# ZVS_Flyback_Driver_Circuit.net
KiCad netlist of a schematic drawn in EAGLE
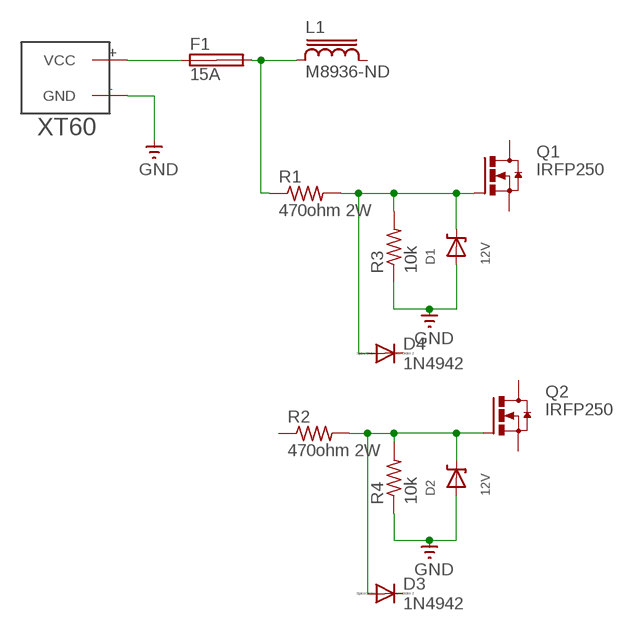
[diagram p0: schematic, sheet 1]

(export (version "E")
  (design (tool "Eeschema 10.0.6"))
  (components
    (comp (ref "D1")
      (value "12V")
      (footprint "eagle-import:SMADIODE")
      (libsource (lib "eagle-import") (part "DIODE-ZENER"))
    )
    (comp (ref "D2")
      (value "12V")
      (footprint "eagle-import:SMADIODE")
      (libsource (lib "eagle-import") (part "DIODE-ZENER"))
    )
    (comp (ref "D3")
      (value "1N4942")
      (footprint "eagle-import:DO41-10")
      (libsource (lib "eagle-import") (part "1N4942"))
    )
    (comp (ref "D4")
      (value "1N4942")
      (footprint "eagle-import:DO41-10")
      (libsource (lib "eagle-import") (part "1N4942"))
    )
    (comp (ref "F1")
      (value "15A")
      (footprint "eagle-import:SHK20L")
      (libsource (lib "eagle-import") (part "SHK20L"))
    )
    (comp (ref "L1")
      (value "M8936-ND")
      (footprint "eagle-import:2320-V-RC")
      (libsource (lib "eagle-import") (part "2300-V"))
    )
    (comp (ref "Q1")
      (value "IRFP250")
      (footprint "eagle-import:TO-247AD-V")
      (libsource (lib "eagle-import") (part "IRFP250"))
    )
    (comp (ref "Q2")
      (value "IRFP250")
      (footprint "eagle-import:TO-247AD-V")
      (libsource (lib "eagle-import") (part "IRFP250"))
    )
    (comp (ref "R1")
      (value "470ohm 2W")
      (footprint "eagle-import:0617_22")
      (libsource (lib "eagle-import") (part "R-US_0617/22"))
    )
    (comp (ref "R2")
      (value "470ohm 2W")
      (footprint "eagle-import:0617_22")
      (libsource (lib "eagle-import") (part "R-US_0617/22"))
    )
    (comp (ref "R3")
      (value "10k")
      (footprint "eagle-import:M0805")
      (libsource (lib "eagle-import") (part "R-US_M0805"))
    )
    (comp (ref "R4")
      (value "10k")
      (footprint "eagle-import:M0805")
      (libsource (lib "eagle-import") (part "R-US_M0805"))
    )
    (comp (ref "U$1")
      (value "XT60")
      (footprint "eagle-import:XT60")
      (libsource (lib "eagle-import") (part "XT60"))
    )
  )
  (nets
    (net (code "1") (name "GND") (class "Default")
      (node (ref "D1") (pin "A") (pinfunction "A_A") (pintype "passive"))
      (node (ref "D2") (pin "A") (pinfunction "A_A") (pintype "passive"))
      (node (ref "R3") (pin "1") (pinfunction "1_1") (pintype "passive"))
      (node (ref "R4") (pin "1") (pinfunction "1_1") (pintype "passive"))
      (node (ref "U$1") (pin "-") (pinfunction "GND_-") (pintype "bidirectional"))
    )
    (net (code "2") (name "Net-(D1-PadC)") (class "Default")
      (node (ref "D1") (pin "C") (pinfunction "C_C") (pintype "passive"))
      (node (ref "D4") (pin "A") (pinfunction "A_A") (pintype "passive"))
      (node (ref "Q1") (pin "G") (pinfunction "G_G") (pintype "passive"))
      (node (ref "R1") (pin "2") (pinfunction "2_2") (pintype "passive"))
      (node (ref "R3") (pin "2") (pinfunction "2_2") (pintype "passive"))
    )
    (net (code "3") (name "Net-(D2-PadC)") (class "Default")
      (node (ref "D2") (pin "C") (pinfunction "C_C") (pintype "passive"))
      (node (ref "D3") (pin "A") (pinfunction "A_A") (pintype "passive"))
      (node (ref "Q2") (pin "G") (pinfunction "G_G") (pintype "passive"))
      (node (ref "R2") (pin "2") (pinfunction "2_2") (pintype "passive"))
      (node (ref "R4") (pin "2") (pinfunction "2_2") (pintype "passive"))
    )
    (net (code "4") (name "Net-(F1-Pad2A)") (class "Default")
      (node (ref "F1") (pin "2A") (pinfunction "2A_2A") (pintype "passive"))
      (node (ref "L1") (pin "1") (pinfunction "1_1") (pintype "passive"))
      (node (ref "R1") (pin "1") (pinfunction "1_1") (pintype "passive"))
    )
    (net (code "5") (name "Net-(U$1-VCC)") (class "Default")
      (node (ref "F1") (pin "1A") (pinfunction "1A_1A") (pintype "passive"))
      (node (ref "U$1") (pin "+") (pinfunction "VCC_+") (pintype "bidirectional"))
    )
    (net (code "6") (name "unconnected-(D3-PadC)") (class "Default")
      (node (ref "D3") (pin "C") (pinfunction "C_C") (pintype "passive"))
    )
    (net (code "7") (name "unconnected-(D4-PadC)") (class "Default")
      (node (ref "D4") (pin "C") (pinfunction "C_C") (pintype "passive"))
    )
    (net (code "8") (name "unconnected-(F1-Pad1B)") (class "Default")
      (node (ref "F1") (pin "1B") (pinfunction "1B_1B") (pintype "passive"))
    )
    (net (code "9") (name "unconnected-(F1-Pad2B)") (class "Default")
      (node (ref "F1") (pin "2B") (pinfunction "2B_2B") (pintype "passive"))
    )
    (net (code "10") (name "unconnected-(L1-Pad2)") (class "Default")
      (node (ref "L1") (pin "2") (pinfunction "2_2") (pintype "passive"))
    )
    (net (code "11") (name "unconnected-(Q1-PadD)") (class "Default")
      (node (ref "Q1") (pin "D") (pinfunction "D_D") (pintype "passive"))
    )
    (net (code "12") (name "unconnected-(Q1-PadS)") (class "Default")
      (node (ref "Q1") (pin "S") (pinfunction "S_S") (pintype "passive"))
    )
    (net (code "13") (name "unconnected-(Q2-PadD)") (class "Default")
      (node (ref "Q2") (pin "D") (pinfunction "D_D") (pintype "passive"))
    )
    (net (code "14") (name "unconnected-(Q2-PadS)") (class "Default")
      (node (ref "Q2") (pin "S") (pinfunction "S_S") (pintype "passive"))
    )
    (net (code "15") (name "unconnected-(R2-Pad1)") (class "Default")
      (node (ref "R2") (pin "1") (pinfunction "1_1") (pintype "passive"))
    )
  )
)
